# sch.net
KiCad netlist of a schematic drawn in EAGLE
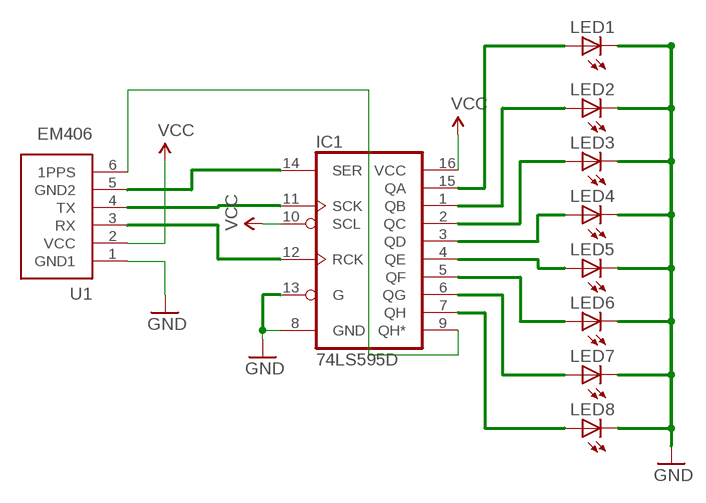
[diagram p0: schematic, sheet 1]

(export (version "E")
  (design (tool "Eeschema 10.0.6"))
  (components
    (comp (ref "IC1")
      (value "74LS595D")
      (footprint "eagle-import:SO16")
      (libsource (lib "eagle-import") (part "74595DLS"))
    )
    (comp (ref "LED1")
      (value "LED1206")
      (footprint "eagle-import:LED-1206")
      (libsource (lib "eagle-import") (part "LED1206"))
    )
    (comp (ref "LED2")
      (value "LED1206")
      (footprint "eagle-import:LED-1206")
      (libsource (lib "eagle-import") (part "LED1206"))
    )
    (comp (ref "LED3")
      (value "LED1206")
      (footprint "eagle-import:LED-1206")
      (libsource (lib "eagle-import") (part "LED1206"))
    )
    (comp (ref "LED4")
      (value "LED1206")
      (footprint "eagle-import:LED-1206")
      (libsource (lib "eagle-import") (part "LED1206"))
    )
    (comp (ref "LED5")
      (value "LED1206")
      (footprint "eagle-import:LED-1206")
      (libsource (lib "eagle-import") (part "LED1206"))
    )
    (comp (ref "LED6")
      (value "LED1206")
      (footprint "eagle-import:LED-1206")
      (libsource (lib "eagle-import") (part "LED1206"))
    )
    (comp (ref "LED7")
      (value "LED1206")
      (footprint "eagle-import:LED-1206")
      (libsource (lib "eagle-import") (part "LED1206"))
    )
    (comp (ref "LED8")
      (value "LED1206")
      (footprint "eagle-import:LED-1206")
      (libsource (lib "eagle-import") (part "LED1206"))
    )
    (comp (ref "U1")
      (value "EM406")
      (footprint "eagle-import:EM406")
      (libsource (lib "eagle-import") (part "EM406"))
    )
  )
  (nets
    (net (code "1") (name "GND") (class "Default")
      (node (ref "IC1") (pin "13") (pinfunction "G_13") (pintype "input"))
      (node (ref "IC1") (pin "8") (pinfunction "GND_8") (pintype "power_in"))
      (node (ref "LED1") (pin "C") (pinfunction "C_C") (pintype "passive"))
      (node (ref "LED2") (pin "C") (pinfunction "C_C") (pintype "passive"))
      (node (ref "LED3") (pin "C") (pinfunction "C_C") (pintype "passive"))
      (node (ref "LED4") (pin "C") (pinfunction "C_C") (pintype "passive"))
      (node (ref "LED5") (pin "C") (pinfunction "C_C") (pintype "passive"))
      (node (ref "LED6") (pin "C") (pinfunction "C_C") (pintype "passive"))
      (node (ref "LED7") (pin "C") (pinfunction "C_C") (pintype "passive"))
      (node (ref "LED8") (pin "C") (pinfunction "C_C") (pintype "passive"))
      (node (ref "U1") (pin "1") (pinfunction "GND1_1") (pintype "bidirectional"))
    )
    (net (code "2") (name "Net-(IC1-QA)") (class "Default")
      (node (ref "IC1") (pin "15") (pinfunction "QA_15") (pintype "tri_state"))
      (node (ref "LED1") (pin "A") (pinfunction "A_A") (pintype "passive"))
    )
    (net (code "3") (name "Net-(IC1-QB)") (class "Default")
      (node (ref "IC1") (pin "1") (pinfunction "QB_1") (pintype "tri_state"))
      (node (ref "LED2") (pin "A") (pinfunction "A_A") (pintype "passive"))
    )
    (net (code "4") (name "Net-(IC1-QC)") (class "Default")
      (node (ref "IC1") (pin "2") (pinfunction "QC_2") (pintype "tri_state"))
      (node (ref "LED3") (pin "A") (pinfunction "A_A") (pintype "passive"))
    )
    (net (code "5") (name "Net-(IC1-QD)") (class "Default")
      (node (ref "IC1") (pin "3") (pinfunction "QD_3") (pintype "tri_state"))
      (node (ref "LED4") (pin "A") (pinfunction "A_A") (pintype "passive"))
    )
    (net (code "6") (name "Net-(IC1-QE)") (class "Default")
      (node (ref "IC1") (pin "4") (pinfunction "QE_4") (pintype "tri_state"))
      (node (ref "LED5") (pin "A") (pinfunction "A_A") (pintype "passive"))
    )
    (net (code "7") (name "Net-(IC1-QF)") (class "Default")
      (node (ref "IC1") (pin "5") (pinfunction "QF_5") (pintype "tri_state"))
      (node (ref "LED6") (pin "A") (pinfunction "A_A") (pintype "passive"))
    )
    (net (code "8") (name "Net-(IC1-QG)") (class "Default")
      (node (ref "IC1") (pin "6") (pinfunction "QG_6") (pintype "tri_state"))
      (node (ref "LED7") (pin "A") (pinfunction "A_A") (pintype "passive"))
    )
    (net (code "9") (name "Net-(IC1-QH)") (class "Default")
      (node (ref "IC1") (pin "7") (pinfunction "QH_7") (pintype "tri_state"))
      (node (ref "LED8") (pin "A") (pinfunction "A_A") (pintype "passive"))
    )
    (net (code "10") (name "Net-(IC1-QH*)") (class "Default")
      (node (ref "IC1") (pin "9") (pinfunction "QH*_9") (pintype "tri_state"))
      (node (ref "U1") (pin "6") (pinfunction "1PPS_6") (pintype "bidirectional"))
    )
    (net (code "11") (name "Net-(IC1-RCK)") (class "Default")
      (node (ref "IC1") (pin "12") (pinfunction "RCK_12") (pintype "input"))
      (node (ref "U1") (pin "3") (pinfunction "RX_3") (pintype "bidirectional"))
    )
    (net (code "12") (name "Net-(IC1-SCK)") (class "Default")
      (node (ref "IC1") (pin "11") (pinfunction "SCK_11") (pintype "input"))
      (node (ref "U1") (pin "4") (pinfunction "TX_4") (pintype "bidirectional"))
    )
    (net (code "13") (name "Net-(IC1-SER)") (class "Default")
      (node (ref "IC1") (pin "14") (pinfunction "SER_14") (pintype "input"))
      (node (ref "U1") (pin "5") (pinfunction "GND2_5") (pintype "bidirectional"))
    )
    (net (code "14") (name "VCC") (class "Default")
      (node (ref "IC1") (pin "10") (pinfunction "SCL_10") (pintype "input"))
      (node (ref "IC1") (pin "16") (pinfunction "VCC_16") (pintype "power_in"))
      (node (ref "U1") (pin "2") (pinfunction "VCC_2") (pintype "bidirectional"))
    )
  )
)
